# Sheet1.net
KiCad netlist of a schematic drawn in Altium Designer
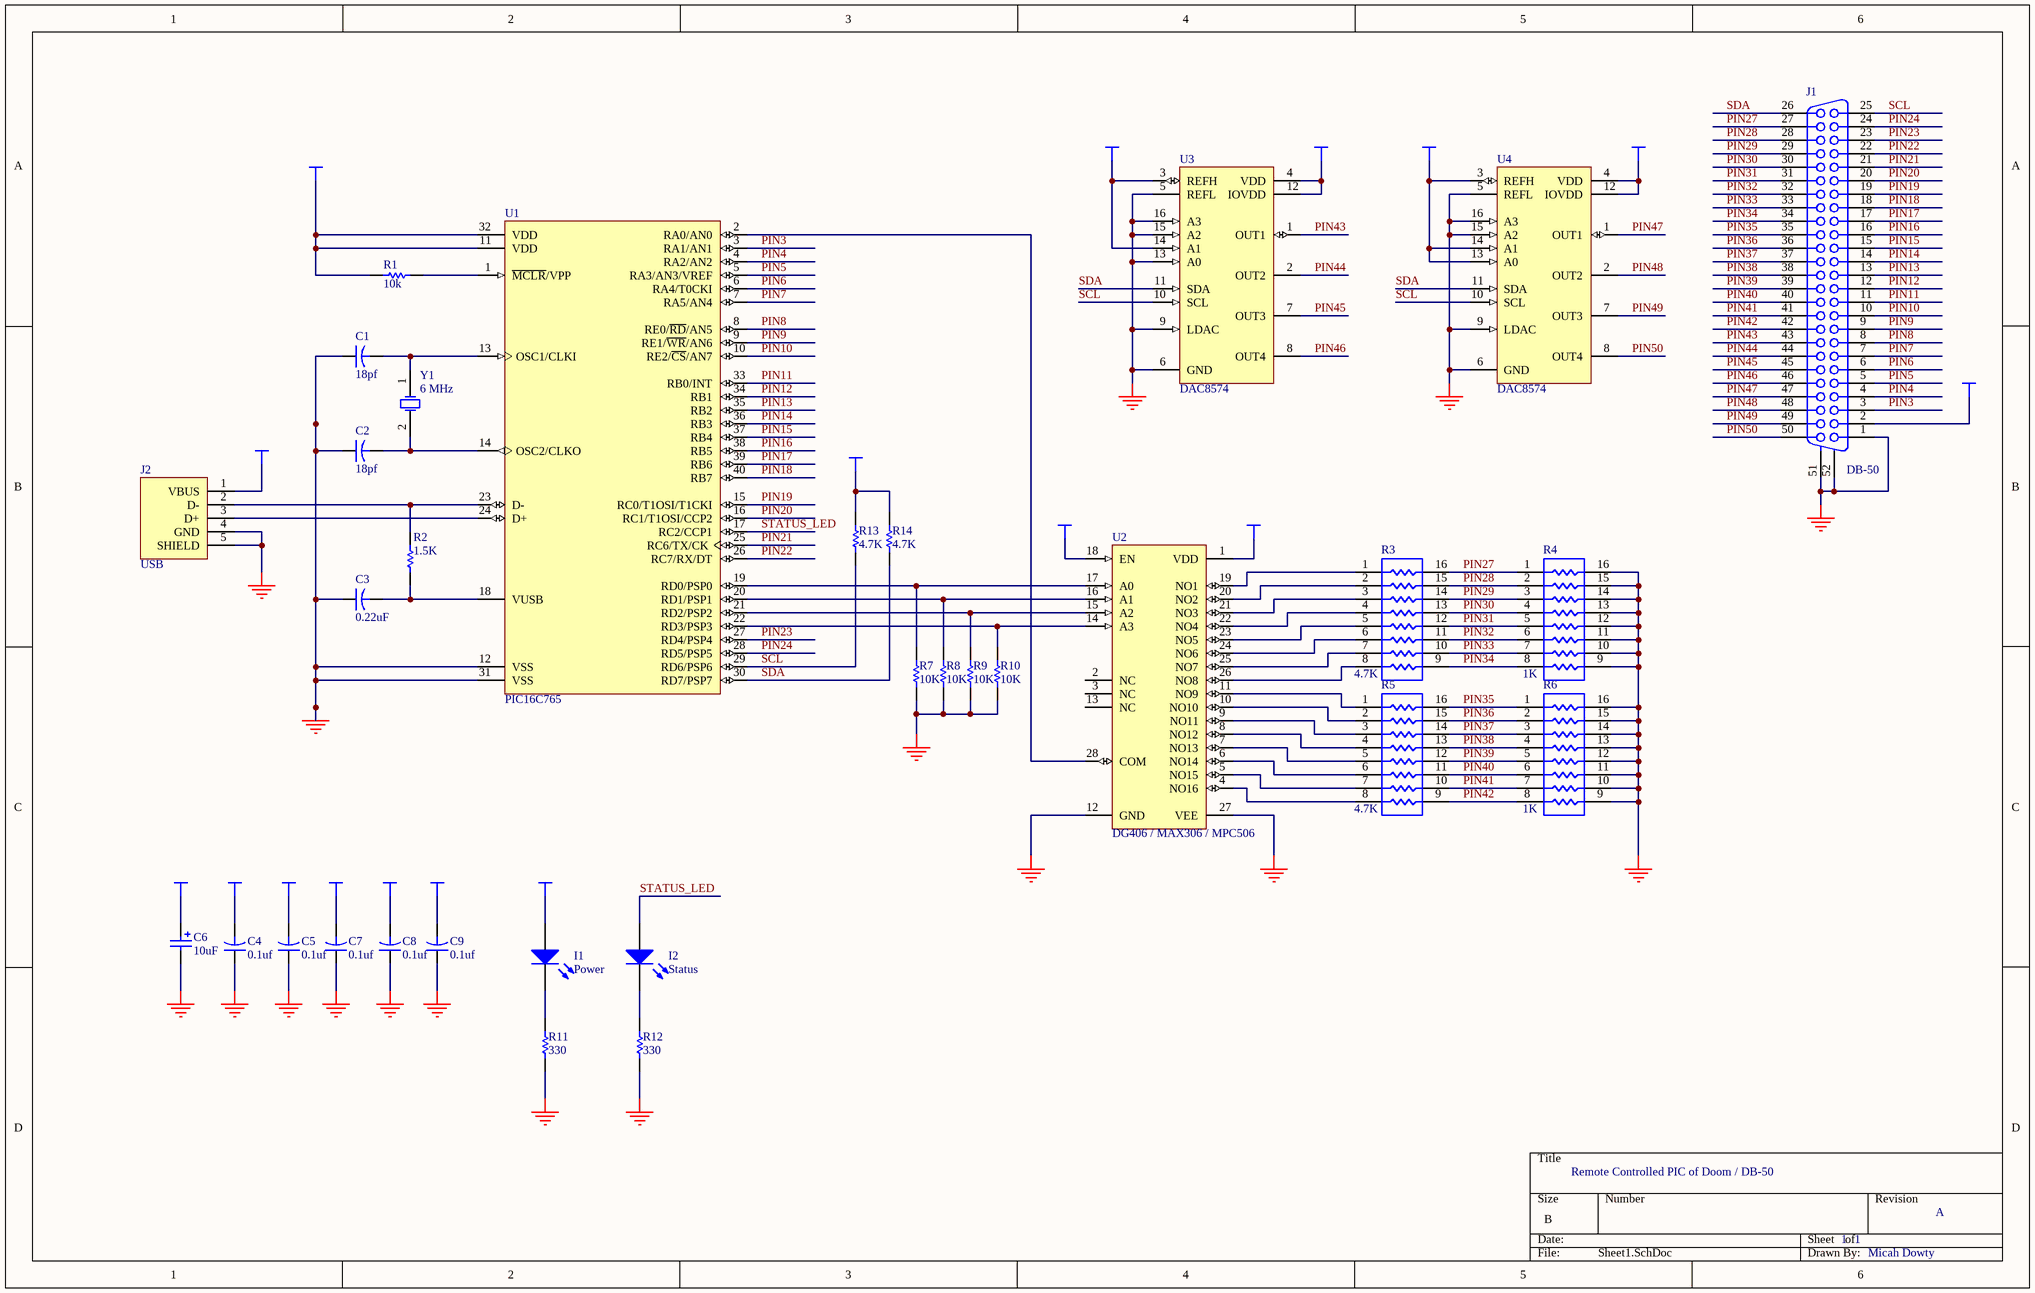
[diagram p0: Sheet1.SchDoc]

(export (version "E")
  (design (tool "Eeschema 10.0.6"))
  (components
    (comp (ref "C1")
      (value "Cap2")
      (footprint "C1005-0402")
      (description "Capacitor")
      (fields
        (field (name "MANUFACTURER") "Generic Components")
        (field (name "ALTIUM_VALUE") "18pf")
        (field (name "PUBLISHER") "Altium Limited")
      )
      (libsource (lib "Miscellaneous Devices") (part "Cap2"))
    )
    (comp (ref "C2")
      (value "Cap2")
      (footprint "C1005-0402")
      (description "Capacitor")
      (fields
        (field (name "MANUFACTURER") "Generic Components")
        (field (name "ALTIUM_VALUE") "18pf")
        (field (name "PUBLISHER") "Altium Limited")
      )
      (libsource (lib "Miscellaneous Devices") (part "Cap2"))
    )
    (comp (ref "C3")
      (value "0.22uF")
      (footprint "C1005-0402")
      (description "Capacitor")
      (fields (field (name "MANUFACTURER") "Generic Components") (field (name "PUBLISHER") "Altium Limited"))
      (libsource (lib "Miscellaneous Devices") (part "Cap2"))
    )
    (comp (ref "C4")
      (value "0.1uf")
      (footprint "C1005-0402")
      (description "Capacitor")
      (fields (field (name "MANUFACTURER") "Generic Components") (field (name "PUBLISHER") "Altium Limited"))
      (libsource (lib "Miscellaneous Devices") (part "Cap2"))
    )
    (comp (ref "C5")
      (value "0.1uf")
      (footprint "C1005-0402")
      (description "Capacitor")
      (fields (field (name "MANUFACTURER") "Generic Components") (field (name "PUBLISHER") "Altium Limited"))
      (libsource (lib "Miscellaneous Devices") (part "Cap2"))
    )
    (comp (ref "C6")
      (value "10uF")
      (footprint "SO-C2/X4.4")
      (description "Polarized Capacitor (Radial)")
      (fields (field (name "MANUFACTURER") "Generic Components") (field (name "PUBLISHER") "Altium Limited"))
      (libsource (lib "Miscellaneous Devices") (part "Cap Pol1"))
    )
    (comp (ref "C7")
      (value "0.1uf")
      (footprint "C1005-0402")
      (description "Capacitor")
      (fields (field (name "MANUFACTURER") "Generic Components") (field (name "PUBLISHER") "Altium Limited"))
      (libsource (lib "Miscellaneous Devices") (part "Cap2"))
    )
    (comp (ref "C8")
      (value "0.1uf")
      (footprint "C1005-0402")
      (description "Capacitor")
      (fields (field (name "MANUFACTURER") "Generic Components") (field (name "PUBLISHER") "Altium Limited"))
      (libsource (lib "Miscellaneous Devices") (part "Cap2"))
    )
    (comp (ref "C9")
      (value "0.1uf")
      (footprint "C1005-0402")
      (description "Capacitor")
      (fields (field (name "MANUFACTURER") "Generic Components") (field (name "PUBLISHER") "Altium Limited"))
      (libsource (lib "Miscellaneous Devices") (part "Cap2"))
    )
    (comp (ref "I1")
      (value "Power")
      (footprint "LED-1-UNBROKE")
      (description "Typical RED GaAs LED")
      (fields (field (name "MANUFACTURER") "Generic Components") (field (name "PUBLISHER") "Altium Limited"))
      (libsource (lib "Miscellaneous Devices") (part "LED1"))
    )
    (comp (ref "I2")
      (value "Status")
      (footprint "LED-1-UNBROKE")
      (description "Typical RED GaAs LED")
      (fields (field (name "MANUFACTURER") "Generic Components") (field (name "PUBLISHER") "Altium Limited"))
      (libsource (lib "Miscellaneous Devices") (part "LED1"))
    )
    (comp (ref "J1")
      (value "DB-50")
      (footprint "CHAMP1.27-2H50-SIMPLE")
      (description "Receptacle Header Assemby")
      (fields (field (name "MANUFACTURER") "Generic Components") (field (name "PUBLISHER") "Altium Limited"))
      (libsource (lib "Miscellaneous Connectors") (part "Connector 50"))
    )
    (comp (ref "J2")
      (value "USB")
      (footprint "USB-TYPEB")
      (description "Header, 4-Pin")
      (fields (field (name "MANUFACTURER") "Generic Components") (field (name "PUBLISHER") "Altium Limited"))
      (libsource (lib "parts") (part "USB Type B"))
    )
    (comp (ref "R1")
      (value "Res1")
      (footprint "C1005-0402")
      (description "Resistor")
      (fields
        (field (name "MANUFACTURER") "Generic Components")
        (field (name "ALTIUM_VALUE") "10k")
        (field (name "PUBLISHER") "Altium Limited")
      )
      (libsource (lib "Miscellaneous Devices") (part "Res1"))
    )
    (comp (ref "R2")
      (value "Res1")
      (footprint "C1005-0402")
      (description "Resistor")
      (fields
        (field (name "MANUFACTURER") "Generic Components")
        (field (name "ALTIUM_VALUE") "1.5K")
        (field (name "PUBLISHER") "Altium Limited")
      )
      (libsource (lib "Miscellaneous Devices") (part "Res1"))
    )
    (comp (ref "R3")
      (value "4.7K")
      (footprint "EXB2HV")
      (description "Resistor Array")
      (fields (field (name "MANUFACTURER") "Generic Components") (field (name "PUBLISHER") "Altium Limited"))
      (libsource (lib "Miscellaneous Devices") (part "Res Pack3"))
    )
    (comp (ref "R4")
      (value "1K")
      (footprint "EXB2HV")
      (description "Resistor Array")
      (fields (field (name "MANUFACTURER") "Generic Components") (field (name "PUBLISHER") "Altium Limited"))
      (libsource (lib "Miscellaneous Devices") (part "Res Pack3"))
    )
    (comp (ref "R5")
      (value "4.7K")
      (footprint "EXB2HV")
      (description "Resistor Array")
      (fields (field (name "MANUFACTURER") "Generic Components") (field (name "PUBLISHER") "Altium Limited"))
      (libsource (lib "Miscellaneous Devices") (part "Res Pack3"))
    )
    (comp (ref "R6")
      (value "1K")
      (footprint "EXB2HV")
      (description "Resistor Array")
      (fields (field (name "MANUFACTURER") "Generic Components") (field (name "PUBLISHER") "Altium Limited"))
      (libsource (lib "Miscellaneous Devices") (part "Res Pack3"))
    )
    (comp (ref "R7")
      (value "10K")
      (footprint "C1005-0402")
      (description "Resistor")
      (fields (field (name "MANUFACTURER") "Generic Components") (field (name "PUBLISHER") "Altium Limited"))
      (libsource (lib "Miscellaneous Devices") (part "Res1"))
    )
    (comp (ref "R8")
      (value "10K")
      (footprint "C1005-0402")
      (description "Resistor")
      (fields (field (name "MANUFACTURER") "Generic Components") (field (name "PUBLISHER") "Altium Limited"))
      (libsource (lib "Miscellaneous Devices") (part "Res1"))
    )
    (comp (ref "R9")
      (value "10K")
      (footprint "C1005-0402")
      (description "Resistor")
      (fields (field (name "MANUFACTURER") "Generic Components") (field (name "PUBLISHER") "Altium Limited"))
      (libsource (lib "Miscellaneous Devices") (part "Res1"))
    )
    (comp (ref "R10")
      (value "10K")
      (footprint "C1005-0402")
      (description "Resistor")
      (fields (field (name "MANUFACTURER") "Generic Components") (field (name "PUBLISHER") "Altium Limited"))
      (libsource (lib "Miscellaneous Devices") (part "Res1"))
    )
    (comp (ref "R11")
      (value "330")
      (footprint "C1005-0402")
      (description "Resistor")
      (fields (field (name "MANUFACTURER") "Generic Components") (field (name "PUBLISHER") "Altium Limited"))
      (libsource (lib "Miscellaneous Devices") (part "Res1"))
    )
    (comp (ref "R12")
      (value "330")
      (footprint "C1005-0402")
      (description "Resistor")
      (fields (field (name "MANUFACTURER") "Generic Components") (field (name "PUBLISHER") "Altium Limited"))
      (libsource (lib "Miscellaneous Devices") (part "Res1"))
    )
    (comp (ref "R13")
      (value "4.7K")
      (footprint "C1005-0402")
      (description "Resistor")
      (fields (field (name "MANUFACTURER") "Generic Components") (field (name "PUBLISHER") "Altium Limited"))
      (libsource (lib "Miscellaneous Devices") (part "Res1"))
    )
    (comp (ref "R14")
      (value "4.7K")
      (footprint "C1005-0402")
      (description "Resistor")
      (fields (field (name "MANUFACTURER") "Generic Components") (field (name "PUBLISHER") "Altium Limited"))
      (libsource (lib "Miscellaneous Devices") (part "Res1"))
    )
    (comp (ref "U1")
      (value "PIC16C765")
      (footprint "DIP-40")
      (description "EPROM-Based 8-Bit CMOS Microcontroller with USB")
      (fields (field (name "MANUFACTURER") "Microchip"))
      (libsource (lib "parts") (part "PIC16C765"))
    )
    (comp (ref "U2")
      (value "DG406 / MAX306 / MPC506")
      (footprint "SO-G28/G7.45")
      (description "Precision, 16-Channel High-performance, CMOS Analog Multiplexer")
      (fields (field (name "MANUFACTURER") "Maxim") (field (name "PUBLISHER") "Altium Limited"))
      (libsource (lib "Maxim Logic Multiplexer") (part "MAX306EPI"))
    )
    (comp (ref "U3")
      (value "DAC8574")
      (footprint "TSSO5X6-G16")
      (description "Quad 16-Bit Low Power Voltage Output I2C Interface DAC")
      (fields (field (name "MANUFACTURER") "Texas Instruments"))
      (libsource (lib "parts") (part "DAC8574"))
    )
    (comp (ref "U4")
      (value "DAC8574")
      (footprint "TSSO5X6-G16")
      (description "Quad 16-Bit Low Power Voltage Output I2C Interface DAC")
      (fields (field (name "MANUFACTURER") "Texas Instruments"))
      (libsource (lib "parts") (part "DAC8574"))
    )
    (comp (ref "Y1")
      (value "6 MHz")
      (footprint "BCY-W2/E4.7")
      (description "Crystal Oscillator")
      (fields (field (name "MANUFACTURER") "Generic Components") (field (name "PUBLISHER") "Altium Limited"))
      (libsource (lib "Miscellaneous Devices") (part "XTAL"))
    )
  )
  (nets
    (net (code "1") (name "/PIN3") (class "Default")
      (node (ref "J1") (pin "3") (pinfunction "3_3") (pintype "passive"))
      (node (ref "U1") (pin "3") (pinfunction "RA1/AN1_3") (pintype "bidirectional"))
    )
    (net (code "2") (name "/PIN4") (class "Default")
      (node (ref "J1") (pin "4") (pinfunction "4_4") (pintype "passive"))
      (node (ref "U1") (pin "4") (pinfunction "RA2/AN2_4") (pintype "bidirectional"))
    )
    (net (code "3") (name "/PIN5") (class "Default")
      (node (ref "J1") (pin "5") (pinfunction "5_5") (pintype "passive"))
      (node (ref "U1") (pin "5") (pinfunction "RA3/AN3/VREF_5") (pintype "bidirectional"))
    )
    (net (code "4") (name "/PIN6") (class "Default")
      (node (ref "J1") (pin "6") (pinfunction "6_6") (pintype "passive"))
      (node (ref "U1") (pin "6") (pinfunction "RA4/T0CKI_6") (pintype "bidirectional"))
    )
    (net (code "5") (name "/PIN7") (class "Default")
      (node (ref "J1") (pin "7") (pinfunction "7_7") (pintype "passive"))
      (node (ref "U1") (pin "7") (pinfunction "RA5/AN4_7") (pintype "bidirectional"))
    )
    (net (code "6") (name "/PIN8") (class "Default")
      (node (ref "J1") (pin "8") (pinfunction "8_8") (pintype "passive"))
      (node (ref "U1") (pin "8") (pinfunction "RE0/~{RD}/AN5_8") (pintype "bidirectional"))
    )
    (net (code "7") (name "/PIN9") (class "Default")
      (node (ref "J1") (pin "9") (pinfunction "9_9") (pintype "passive"))
      (node (ref "U1") (pin "9") (pinfunction "RE1/~{WR}/AN6_9") (pintype "bidirectional"))
    )
    (net (code "8") (name "/PIN10") (class "Default")
      (node (ref "J1") (pin "10") (pinfunction "10_10") (pintype "passive"))
      (node (ref "U1") (pin "10") (pinfunction "RE2/~{CS}/AN7_10") (pintype "bidirectional"))
    )
    (net (code "9") (name "/PIN11") (class "Default")
      (node (ref "J1") (pin "11") (pinfunction "11_11") (pintype "passive"))
      (node (ref "U1") (pin "33") (pinfunction "RB0/INT_33") (pintype "bidirectional"))
    )
    (net (code "10") (name "/PIN12") (class "Default")
      (node (ref "J1") (pin "12") (pinfunction "12_12") (pintype "passive"))
      (node (ref "U1") (pin "34") (pinfunction "RB1_34") (pintype "bidirectional"))
    )
    (net (code "11") (name "/PIN13") (class "Default")
      (node (ref "J1") (pin "13") (pinfunction "13_13") (pintype "passive"))
      (node (ref "U1") (pin "35") (pinfunction "RB2_35") (pintype "bidirectional"))
    )
    (net (code "12") (name "/PIN14") (class "Default")
      (node (ref "J1") (pin "14") (pinfunction "14_14") (pintype "passive"))
      (node (ref "U1") (pin "36") (pinfunction "RB3_36") (pintype "bidirectional"))
    )
    (net (code "13") (name "/PIN15") (class "Default")
      (node (ref "J1") (pin "15") (pinfunction "15_15") (pintype "passive"))
      (node (ref "U1") (pin "37") (pinfunction "RB4_37") (pintype "bidirectional"))
    )
    (net (code "14") (name "/PIN16") (class "Default")
      (node (ref "J1") (pin "16") (pinfunction "16_16") (pintype "passive"))
      (node (ref "U1") (pin "38") (pinfunction "RB5_38") (pintype "bidirectional"))
    )
    (net (code "15") (name "/PIN17") (class "Default")
      (node (ref "J1") (pin "17") (pinfunction "17_17") (pintype "passive"))
      (node (ref "U1") (pin "39") (pinfunction "RB6_39") (pintype "bidirectional"))
    )
    (net (code "16") (name "/PIN18") (class "Default")
      (node (ref "J1") (pin "18") (pinfunction "18_18") (pintype "passive"))
      (node (ref "U1") (pin "40") (pinfunction "RB7_40") (pintype "bidirectional"))
    )
    (net (code "17") (name "/PIN19") (class "Default")
      (node (ref "J1") (pin "19") (pinfunction "19_19") (pintype "passive"))
      (node (ref "U1") (pin "15") (pinfunction "RC0/T1OSI/T1CKI_15") (pintype "bidirectional"))
    )
    (net (code "18") (name "/PIN20") (class "Default")
      (node (ref "J1") (pin "20") (pinfunction "20_20") (pintype "passive"))
      (node (ref "U1") (pin "16") (pinfunction "RC1/T1OSI/CCP2_16") (pintype "bidirectional"))
    )
    (net (code "19") (name "/PIN21") (class "Default")
      (node (ref "J1") (pin "21") (pinfunction "21_21") (pintype "passive"))
      (node (ref "U1") (pin "25") (pinfunction "RC6/TX/CK_25") (pintype "bidirectional"))
    )
    (net (code "20") (name "/PIN22") (class "Default")
      (node (ref "J1") (pin "22") (pinfunction "22_22") (pintype "passive"))
      (node (ref "U1") (pin "26") (pinfunction "RC7/RX/DT_26") (pintype "bidirectional"))
    )
    (net (code "21") (name "/PIN23") (class "Default")
      (node (ref "J1") (pin "23") (pinfunction "23_23") (pintype "passive"))
      (node (ref "U1") (pin "27") (pinfunction "RD4/PSP4_27") (pintype "bidirectional"))
    )
    (net (code "22") (name "/PIN24") (class "Default")
      (node (ref "J1") (pin "24") (pinfunction "24_24") (pintype "passive"))
      (node (ref "U1") (pin "28") (pinfunction "RD5/PSP5_28") (pintype "bidirectional"))
    )
    (net (code "23") (name "/PIN27") (class "Default")
      (node (ref "J1") (pin "27") (pinfunction "27_27") (pintype "passive"))
      (node (ref "R3") (pin "16") (pinfunction "16_16") (pintype "passive"))
      (node (ref "R4") (pin "1") (pinfunction "1_1") (pintype "passive"))
    )
    (net (code "24") (name "/PIN28") (class "Default")
      (node (ref "J1") (pin "28") (pinfunction "28_28") (pintype "passive"))
      (node (ref "R3") (pin "15") (pinfunction "15_15") (pintype "passive"))
      (node (ref "R4") (pin "2") (pinfunction "2_2") (pintype "passive"))
    )
    (net (code "25") (name "/PIN29") (class "Default")
      (node (ref "J1") (pin "29") (pinfunction "29_29") (pintype "passive"))
      (node (ref "R3") (pin "14") (pinfunction "14_14") (pintype "passive"))
      (node (ref "R4") (pin "3") (pinfunction "3_3") (pintype "passive"))
    )
    (net (code "26") (name "/PIN30") (class "Default")
      (node (ref "J1") (pin "30") (pinfunction "30_30") (pintype "passive"))
      (node (ref "R3") (pin "13") (pinfunction "13_13") (pintype "passive"))
      (node (ref "R4") (pin "4") (pinfunction "4_4") (pintype "passive"))
    )
    (net (code "27") (name "/PIN31") (class "Default")
      (node (ref "J1") (pin "31") (pinfunction "31_31") (pintype "passive"))
      (node (ref "R3") (pin "12") (pinfunction "12_12") (pintype "passive"))
      (node (ref "R4") (pin "5") (pinfunction "5_5") (pintype "passive"))
    )
    (net (code "28") (name "/PIN32") (class "Default")
      (node (ref "J1") (pin "32") (pinfunction "32_32") (pintype "passive"))
      (node (ref "R3") (pin "11") (pinfunction "11_11") (pintype "passive"))
      (node (ref "R4") (pin "6") (pinfunction "6_6") (pintype "passive"))
    )
    (net (code "29") (name "/PIN33") (class "Default")
      (node (ref "J1") (pin "33") (pinfunction "33_33") (pintype "passive"))
      (node (ref "R3") (pin "10") (pinfunction "10_10") (pintype "passive"))
      (node (ref "R4") (pin "7") (pinfunction "7_7") (pintype "passive"))
    )
    (net (code "30") (name "/PIN34") (class "Default")
      (node (ref "J1") (pin "34") (pinfunction "34_34") (pintype "passive"))
      (node (ref "R3") (pin "9") (pinfunction "9_9") (pintype "passive"))
      (node (ref "R4") (pin "8") (pinfunction "8_8") (pintype "passive"))
    )
    (net (code "31") (name "/PIN35") (class "Default")
      (node (ref "J1") (pin "35") (pinfunction "35_35") (pintype "passive"))
      (node (ref "R5") (pin "16") (pinfunction "16_16") (pintype "passive"))
      (node (ref "R6") (pin "1") (pinfunction "1_1") (pintype "passive"))
    )
    (net (code "32") (name "/PIN36") (class "Default")
      (node (ref "J1") (pin "36") (pinfunction "36_36") (pintype "passive"))
      (node (ref "R5") (pin "15") (pinfunction "15_15") (pintype "passive"))
      (node (ref "R6") (pin "2") (pinfunction "2_2") (pintype "passive"))
    )
    (net (code "33") (name "/PIN37") (class "Default")
      (node (ref "J1") (pin "37") (pinfunction "37_37") (pintype "passive"))
      (node (ref "R5") (pin "14") (pinfunction "14_14") (pintype "passive"))
      (node (ref "R6") (pin "3") (pinfunction "3_3") (pintype "passive"))
    )
    (net (code "34") (name "/PIN38") (class "Default")
      (node (ref "J1") (pin "38") (pinfunction "38_38") (pintype "passive"))
      (node (ref "R5") (pin "13") (pinfunction "13_13") (pintype "passive"))
      (node (ref "R6") (pin "4") (pinfunction "4_4") (pintype "passive"))
    )
    (net (code "35") (name "/PIN39") (class "Default")
      (node (ref "J1") (pin "39") (pinfunction "39_39") (pintype "passive"))
      (node (ref "R5") (pin "12") (pinfunction "12_12") (pintype "passive"))
      (node (ref "R6") (pin "5") (pinfunction "5_5") (pintype "passive"))
    )
    (net (code "36") (name "/PIN40") (class "Default")
      (node (ref "J1") (pin "40") (pinfunction "40_40") (pintype "passive"))
      (node (ref "R5") (pin "11") (pinfunction "11_11") (pintype "passive"))
      (node (ref "R6") (pin "6") (pinfunction "6_6") (pintype "passive"))
    )
    (net (code "37") (name "/PIN41") (class "Default")
      (node (ref "J1") (pin "41") (pinfunction "41_41") (pintype "passive"))
      (node (ref "R5") (pin "10") (pinfunction "10_10") (pintype "passive"))
      (node (ref "R6") (pin "7") (pinfunction "7_7") (pintype "passive"))
    )
    (net (code "38") (name "/PIN42") (class "Default")
      (node (ref "J1") (pin "42") (pinfunction "42_42") (pintype "passive"))
      (node (ref "R5") (pin "9") (pinfunction "9_9") (pintype "passive"))
      (node (ref "R6") (pin "8") (pinfunction "8_8") (pintype "passive"))
    )
    (net (code "39") (name "/PIN43") (class "Default")
      (node (ref "J1") (pin "43") (pinfunction "43_43") (pintype "passive"))
      (node (ref "U3") (pin "1") (pinfunction "OUT1_1") (pintype "bidirectional"))
    )
    (net (code "40") (name "/PIN44") (class "Default")
      (node (ref "J1") (pin "44") (pinfunction "44_44") (pintype "passive"))
      (node (ref "U3") (pin "2") (pinfunction "OUT2_2") (pintype "passive"))
    )
    (net (code "41") (name "/PIN45") (class "Default")
      (node (ref "J1") (pin "45") (pinfunction "45_45") (pintype "passive"))
      (node (ref "U3") (pin "7") (pinfunction "OUT3_7") (pintype "passive"))
    )
    (net (code "42") (name "/PIN46") (class "Default")
      (node (ref "J1") (pin "46") (pinfunction "46_46") (pintype "passive"))
      (node (ref "U3") (pin "8") (pinfunction "OUT4_8") (pintype "passive"))
    )
    (net (code "43") (name "/PIN47") (class "Default")
      (node (ref "J1") (pin "47") (pinfunction "47_47") (pintype "passive"))
      (node (ref "U4") (pin "1") (pinfunction "OUT1_1") (pintype "bidirectional"))
    )
    (net (code "44") (name "/PIN48") (class "Default")
      (node (ref "J1") (pin "48") (pinfunction "48_48") (pintype "passive"))
      (node (ref "U4") (pin "2") (pinfunction "OUT2_2") (pintype "passive"))
    )
    (net (code "45") (name "/PIN49") (class "Default")
      (node (ref "J1") (pin "49") (pinfunction "49_49") (pintype "passive"))
      (node (ref "U4") (pin "7") (pinfunction "OUT3_7") (pintype "passive"))
    )
    (net (code "46") (name "/PIN50") (class "Default")
      (node (ref "J1") (pin "50") (pinfunction "50_50") (pintype "passive"))
      (node (ref "U4") (pin "8") (pinfunction "OUT4_8") (pintype "passive"))
    )
    (net (code "47") (name "/SCL") (class "Default")
      (node (ref "J1") (pin "25") (pinfunction "25_25") (pintype "passive"))
      (node (ref "R13") (pin "1") (pinfunction "1_1") (pintype "passive"))
      (node (ref "U1") (pin "29") (pinfunction "RD6/PSP6_29") (pintype "bidirectional"))
      (node (ref "U3") (pin "10") (pinfunction "SCL_10") (pintype "input"))
      (node (ref "U4") (pin "10") (pinfunction "SCL_10") (pintype "input"))
    )
    (net (code "48") (name "/SDA") (class "Default")
      (node (ref "J1") (pin "26") (pinfunction "26_26") (pintype "passive"))
      (node (ref "R14") (pin "1") (pinfunction "1_1") (pintype "passive"))
      (node (ref "U1") (pin "30") (pinfunction "RD7/PSP7_30") (pintype "bidirectional"))
      (node (ref "U3") (pin "11") (pinfunction "SDA_11") (pintype "input"))
      (node (ref "U4") (pin "11") (pinfunction "SDA_11") (pintype "input"))
    )
    (net (code "49") (name "/STATUS_LED") (class "Default")
      (node (ref "I2") (pin "1") (pinfunction "A_1") (pintype "passive"))
      (node (ref "U1") (pin "17") (pinfunction "RC2/CCP1_17") (pintype "bidirectional"))
    )
    (net (code "50") (name "GND") (class "Default")
      (node (ref "C1") (pin "1") (pinfunction "1_1") (pintype "passive"))
      (node (ref "C2") (pin "1") (pinfunction "1_1") (pintype "passive"))
      (node (ref "C3") (pin "1") (pinfunction "1_1") (pintype "passive"))
      (node (ref "C4") (pin "1") (pinfunction "1_1") (pintype "passive"))
      (node (ref "C5") (pin "1") (pinfunction "1_1") (pintype "passive"))
      (node (ref "C6") (pin "2") (pinfunction "2_2") (pintype "passive"))
      (node (ref "C7") (pin "1") (pinfunction "1_1") (pintype "passive"))
      (node (ref "C8") (pin "1") (pinfunction "1_1") (pintype "passive"))
      (node (ref "C9") (pin "1") (pinfunction "1_1") (pintype "passive"))
      (node (ref "J1") (pin "1") (pinfunction "1_1") (pintype "passive"))
      (node (ref "J1") (pin "51") (pinfunction "MH1_51") (pintype "passive"))
      (node (ref "J1") (pin "52") (pinfunction "MH2_52") (pintype "passive"))
      (node (ref "J2") (pin "4") (pinfunction "GND_4") (pintype "passive"))
      (node (ref "J2") (pin "5") (pinfunction "SHIELD_5") (pintype "power_in"))
      (node (ref "R10") (pin "1") (pinfunction "1_1") (pintype "passive"))
      (node (ref "R11") (pin "2") (pinfunction "2_2") (pintype "passive"))
      (node (ref "R12") (pin "2") (pinfunction "2_2") (pintype "passive"))
      (node (ref "R4") (pin "10") (pinfunction "10_10") (pintype "passive"))
      (node (ref "R4") (pin "11") (pinfunction "11_11") (pintype "passive"))
      (node (ref "R4") (pin "12") (pinfunction "12_12") (pintype "passive"))
      (node (ref "R4") (pin "13") (pinfunction "13_13") (pintype "passive"))
      (node (ref "R4") (pin "14") (pinfunction "14_14") (pintype "passive"))
      (node (ref "R4") (pin "15") (pinfunction "15_15") (pintype "passive"))
      (node (ref "R4") (pin "16") (pinfunction "16_16") (pintype "passive"))
      (node (ref "R4") (pin "9") (pinfunction "9_9") (pintype "passive"))
      (node (ref "R6") (pin "10") (pinfunction "10_10") (pintype "passive"))
      (node (ref "R6") (pin "11") (pinfunction "11_11") (pintype "passive"))
      (node (ref "R6") (pin "12") (pinfunction "12_12") (pintype "passive"))
      (node (ref "R6") (pin "13") (pinfunction "13_13") (pintype "passive"))
      (node (ref "R6") (pin "14") (pinfunction "14_14") (pintype "passive"))
      (node (ref "R6") (pin "15") (pinfunction "15_15") (pintype "passive"))
      (node (ref "R6") (pin "16") (pinfunction "16_16") (pintype "passive"))
      (node (ref "R6") (pin "9") (pinfunction "9_9") (pintype "passive"))
      (node (ref "R7") (pin "1") (pinfunction "1_1") (pintype "passive"))
      (node (ref "R8") (pin "1") (pinfunction "1_1") (pintype "passive"))
      (node (ref "R9") (pin "1") (pinfunction "1_1") (pintype "passive"))
      (node (ref "U1") (pin "12") (pinfunction "VSS_12") (pintype "power_in"))
      (node (ref "U1") (pin "31") (pinfunction "VSS_31") (pintype "power_in"))
      (node (ref "U2") (pin "12") (pinfunction "GND_12") (pintype "power_in"))
      (node (ref "U2") (pin "27") (pinfunction "VEE_27") (pintype "power_in"))
      (node (ref "U3") (pin "13") (pinfunction "A0_13") (pintype "input"))
      (node (ref "U3") (pin "15") (pinfunction "A2_15") (pintype "input"))
      (node (ref "U3") (pin "16") (pinfunction "A3_16") (pintype "input"))
      (node (ref "U3") (pin "5") (pinfunction "REFL_5") (pintype "passive"))
      (node (ref "U3") (pin "6") (pinfunction "GND_6") (pintype "power_in"))
      (node (ref "U3") (pin "9") (pinfunction "LDAC_9") (pintype "input"))
      (node (ref "U4") (pin "15") (pinfunction "A2_15") (pintype "input"))
      (node (ref "U4") (pin "16") (pinfunction "A3_16") (pintype "input"))
      (node (ref "U4") (pin "5") (pinfunction "REFL_5") (pintype "passive"))
      (node (ref "U4") (pin "6") (pinfunction "GND_6") (pintype "power_in"))
      (node (ref "U4") (pin "9") (pinfunction "LDAC_9") (pintype "input"))
    )
    (net (code "51") (name "Net-(I1-K)") (class "Default")
      (node (ref "I1") (pin "2") (pinfunction "K_2") (pintype "passive"))
      (node (ref "R11") (pin "1") (pinfunction "1_1") (pintype "passive"))
    )
    (net (code "52") (name "Net-(I2-K)") (class "Default")
      (node (ref "I2") (pin "2") (pinfunction "K_2") (pintype "passive"))
      (node (ref "R12") (pin "1") (pinfunction "1_1") (pintype "passive"))
    )
    (net (code "53") (name "Net-(J2-D+)") (class "Default")
      (node (ref "J2") (pin "3") (pinfunction "D+_3") (pintype "passive"))
      (node (ref "U1") (pin "24") (pinfunction "D+_24") (pintype "bidirectional"))
    )
    (net (code "54") (name "Net-(J2-D-)") (class "Default")
      (node (ref "J2") (pin "2") (pinfunction "D-_2") (pintype "passive"))
      (node (ref "R2") (pin "2") (pinfunction "2_2") (pintype "passive"))
      (node (ref "U1") (pin "23") (pinfunction "D-_23") (pintype "bidirectional"))
    )
    (net (code "55") (name "Net-(U1-OSC1{slash}CLKI)") (class "Default")
      (node (ref "C1") (pin "2") (pinfunction "2_2") (pintype "passive"))
      (node (ref "U1") (pin "13") (pinfunction "OSC1/CLKI_13") (pintype "input"))
      (node (ref "Y1") (pin "1") (pinfunction "OSC1_1") (pintype "passive"))
    )
    (net (code "56") (name "Net-(U1-OSC2{slash}CLKO)") (class "Default")
      (node (ref "C2") (pin "2") (pinfunction "2_2") (pintype "passive"))
      (node (ref "U1") (pin "14") (pinfunction "OSC2/CLKO_14") (pintype "output"))
      (node (ref "Y1") (pin "2") (pinfunction "OSC2_2") (pintype "passive"))
    )
    (net (code "57") (name "Net-(U1-RA0{slash}AN0)") (class "Default")
      (node (ref "U1") (pin "2") (pinfunction "RA0/AN0_2") (pintype "bidirectional"))
      (node (ref "U2") (pin "28") (pinfunction "COM_28") (pintype "bidirectional"))
    )
    (net (code "58") (name "Net-(U1-RD0{slash}PSP0)") (class "Default")
      (node (ref "R7") (pin "2") (pinfunction "2_2") (pintype "passive"))
      (node (ref "U1") (pin "19") (pinfunction "RD0/PSP0_19") (pintype "bidirectional"))
      (node (ref "U2") (pin "17") (pinfunction "A0_17") (pintype "input"))
    )
    (net (code "59") (name "Net-(U1-RD1{slash}PSP1)") (class "Default")
      (node (ref "R8") (pin "2") (pinfunction "2_2") (pintype "passive"))
      (node (ref "U1") (pin "20") (pinfunction "RD1/PSP1_20") (pintype "bidirectional"))
      (node (ref "U2") (pin "16") (pinfunction "A1_16") (pintype "input"))
    )
    (net (code "60") (name "Net-(U1-RD2{slash}PSP2)") (class "Default")
      (node (ref "R9") (pin "2") (pinfunction "2_2") (pintype "passive"))
      (node (ref "U1") (pin "21") (pinfunction "RD2/PSP2_21") (pintype "bidirectional"))
      (node (ref "U2") (pin "15") (pinfunction "A2_15") (pintype "input"))
    )
    (net (code "61") (name "Net-(U1-RD3{slash}PSP3)") (class "Default")
      (node (ref "R10") (pin "2") (pinfunction "2_2") (pintype "passive"))
      (node (ref "U1") (pin "22") (pinfunction "RD3/PSP3_22") (pintype "bidirectional"))
      (node (ref "U2") (pin "14") (pinfunction "A3_14") (pintype "input"))
    )
    (net (code "62") (name "Net-(U1-VUSB)") (class "Default")
      (node (ref "C3") (pin "2") (pinfunction "2_2") (pintype "passive"))
      (node (ref "R2") (pin "1") (pinfunction "1_1") (pintype "passive"))
      (node (ref "U1") (pin "18") (pinfunction "VUSB_18") (pintype "power_in"))
    )
    (net (code "63") (name "Net-(U1-~{MCLR}{slash}VPP)") (class "Default")
      (node (ref "R1") (pin "1") (pinfunction "1_1") (pintype "passive"))
      (node (ref "U1") (pin "1") (pinfunction "~{MCLR}/VPP_1") (pintype "input"))
    )
    (net (code "64") (name "Net-(U2-NO1)") (class "Default")
      (node (ref "R3") (pin "1") (pinfunction "1_1") (pintype "passive"))
      (node (ref "U2") (pin "19") (pinfunction "NO1_19") (pintype "bidirectional"))
    )
    (net (code "65") (name "Net-(U2-NO2)") (class "Default")
      (node (ref "R3") (pin "2") (pinfunction "2_2") (pintype "passive"))
      (node (ref "U2") (pin "20") (pinfunction "NO2_20") (pintype "bidirectional"))
    )
    (net (code "66") (name "Net-(U2-NO3)") (class "Default")
      (node (ref "R3") (pin "3") (pinfunction "3_3") (pintype "passive"))
      (node (ref "U2") (pin "21") (pinfunction "NO3_21") (pintype "bidirectional"))
    )
    (net (code "67") (name "Net-(U2-NO4)") (class "Default")
      (node (ref "R3") (pin "4") (pinfunction "4_4") (pintype "passive"))
      (node (ref "U2") (pin "22") (pinfunction "NO4_22") (pintype "bidirectional"))
    )
    (net (code "68") (name "Net-(U2-NO5)") (class "Default")
      (node (ref "R3") (pin "5") (pinfunction "5_5") (pintype "passive"))
      (node (ref "U2") (pin "23") (pinfunction "NO5_23") (pintype "bidirectional"))
    )
    (net (code "69") (name "Net-(U2-NO6)") (class "Default")
      (node (ref "R3") (pin "6") (pinfunction "6_6") (pintype "passive"))
      (node (ref "U2") (pin "24") (pinfunction "NO6_24") (pintype "bidirectional"))
    )
    (net (code "70") (name "Net-(U2-NO7)") (class "Default")
      (node (ref "R3") (pin "7") (pinfunction "7_7") (pintype "passive"))
      (node (ref "U2") (pin "25") (pinfunction "NO7_25") (pintype "bidirectional"))
    )
    (net (code "71") (name "Net-(U2-NO8)") (class "Default")
      (node (ref "R3") (pin "8") (pinfunction "8_8") (pintype "passive"))
      (node (ref "U2") (pin "26") (pinfunction "NO8_26") (pintype "bidirectional"))
    )
    (net (code "72") (name "Net-(U2-NO9)") (class "Default")
      (node (ref "R5") (pin "1") (pinfunction "1_1") (pintype "passive"))
      (node (ref "U2") (pin "11") (pinfunction "NO9_11") (pintype "bidirectional"))
    )
    (net (code "73") (name "Net-(U2-NO10)") (class "Default")
      (node (ref "R5") (pin "2") (pinfunction "2_2") (pintype "passive"))
      (node (ref "U2") (pin "10") (pinfunction "NO10_10") (pintype "bidirectional"))
    )
    (net (code "74") (name "Net-(U2-NO11)") (class "Default")
      (node (ref "R5") (pin "3") (pinfunction "3_3") (pintype "passive"))
      (node (ref "U2") (pin "9") (pinfunction "NO11_9") (pintype "bidirectional"))
    )
    (net (code "75") (name "Net-(U2-NO12)") (class "Default")
      (node (ref "R5") (pin "4") (pinfunction "4_4") (pintype "passive"))
      (node (ref "U2") (pin "8") (pinfunction "NO12_8") (pintype "bidirectional"))
    )
    (net (code "76") (name "Net-(U2-NO13)") (class "Default")
      (node (ref "R5") (pin "5") (pinfunction "5_5") (pintype "passive"))
      (node (ref "U2") (pin "7") (pinfunction "NO13_7") (pintype "bidirectional"))
    )
    (net (code "77") (name "Net-(U2-NO14)") (class "Default")
      (node (ref "R5") (pin "6") (pinfunction "6_6") (pintype "passive"))
      (node (ref "U2") (pin "6") (pinfunction "NO14_6") (pintype "bidirectional"))
    )
    (net (code "78") (name "Net-(U2-NO15)") (class "Default")
      (node (ref "R5") (pin "7") (pinfunction "7_7") (pintype "passive"))
      (node (ref "U2") (pin "5") (pinfunction "NO15_5") (pintype "bidirectional"))
    )
    (net (code "79") (name "Net-(U2-NO16)") (class "Default")
      (node (ref "R5") (pin "8") (pinfunction "8_8") (pintype "passive"))
      (node (ref "U2") (pin "4") (pinfunction "NO16_4") (pintype "bidirectional"))
    )
    (net (code "80") (name "VCC") (class "Default")
      (node (ref "C4") (pin "2") (pinfunction "2_2") (pintype "passive"))
      (node (ref "C5") (pin "2") (pinfunction "2_2") (pintype "passive"))
      (node (ref "C6") (pin "1") (pinfunction "1_1") (pintype "passive"))
      (node (ref "C7") (pin "2") (pinfunction "2_2") (pintype "passive"))
      (node (ref "C8") (pin "2") (pinfunction "2_2") (pintype "passive"))
      (node (ref "C9") (pin "2") (pinfunction "2_2") (pintype "passive"))
      (node (ref "I1") (pin "1") (pinfunction "A_1") (pintype "passive"))
      (node (ref "J1") (pin "2") (pinfunction "2_2") (pintype "passive"))
      (node (ref "J2") (pin "1") (pinfunction "VBUS_1") (pintype "passive"))
      (node (ref "R1") (pin "2") (pinfunction "2_2") (pintype "passive"))
      (node (ref "R13") (pin "2") (pinfunction "2_2") (pintype "passive"))
      (node (ref "R14") (pin "2") (pinfunction "2_2") (pintype "passive"))
      (node (ref "U1") (pin "11") (pinfunction "VDD_11") (pintype "power_in"))
      (node (ref "U1") (pin "32") (pinfunction "VDD_32") (pintype "power_in"))
      (node (ref "U2") (pin "1") (pinfunction "VDD_1") (pintype "power_in"))
      (node (ref "U2") (pin "18") (pinfunction "EN_18") (pintype "input"))
      (node (ref "U3") (pin "12") (pinfunction "IOVDD_12") (pintype "power_in"))
      (node (ref "U3") (pin "14") (pinfunction "A1_14") (pintype "input"))
      (node (ref "U3") (pin "3") (pinfunction "REFH_3") (pintype "bidirectional"))
      (node (ref "U3") (pin "4") (pinfunction "VDD_4") (pintype "power_in"))
      (node (ref "U4") (pin "12") (pinfunction "IOVDD_12") (pintype "power_in"))
      (node (ref "U4") (pin "13") (pinfunction "A0_13") (pintype "input"))
      (node (ref "U4") (pin "14") (pinfunction "A1_14") (pintype "input"))
      (node (ref "U4") (pin "3") (pinfunction "REFH_3") (pintype "bidirectional"))
      (node (ref "U4") (pin "4") (pinfunction "VDD_4") (pintype "power_in"))
    )
    (net (code "81") (name "unconnected-(U2-NC-Pad2)") (class "Default")
      (node (ref "U2") (pin "2") (pinfunction "NC_2") (pintype "passive"))
    )
    (net (code "82") (name "unconnected-(U2-NC-Pad3)") (class "Default")
      (node (ref "U2") (pin "3") (pinfunction "NC_3") (pintype "passive"))
    )
    (net (code "83") (name "unconnected-(U2-NC-Pad13)") (class "Default")
      (node (ref "U2") (pin "13") (pinfunction "NC_13") (pintype "passive"))
    )
  )
)
